# s16_panel_2.net
KiCad netlist of a schematic drawn in EAGLE
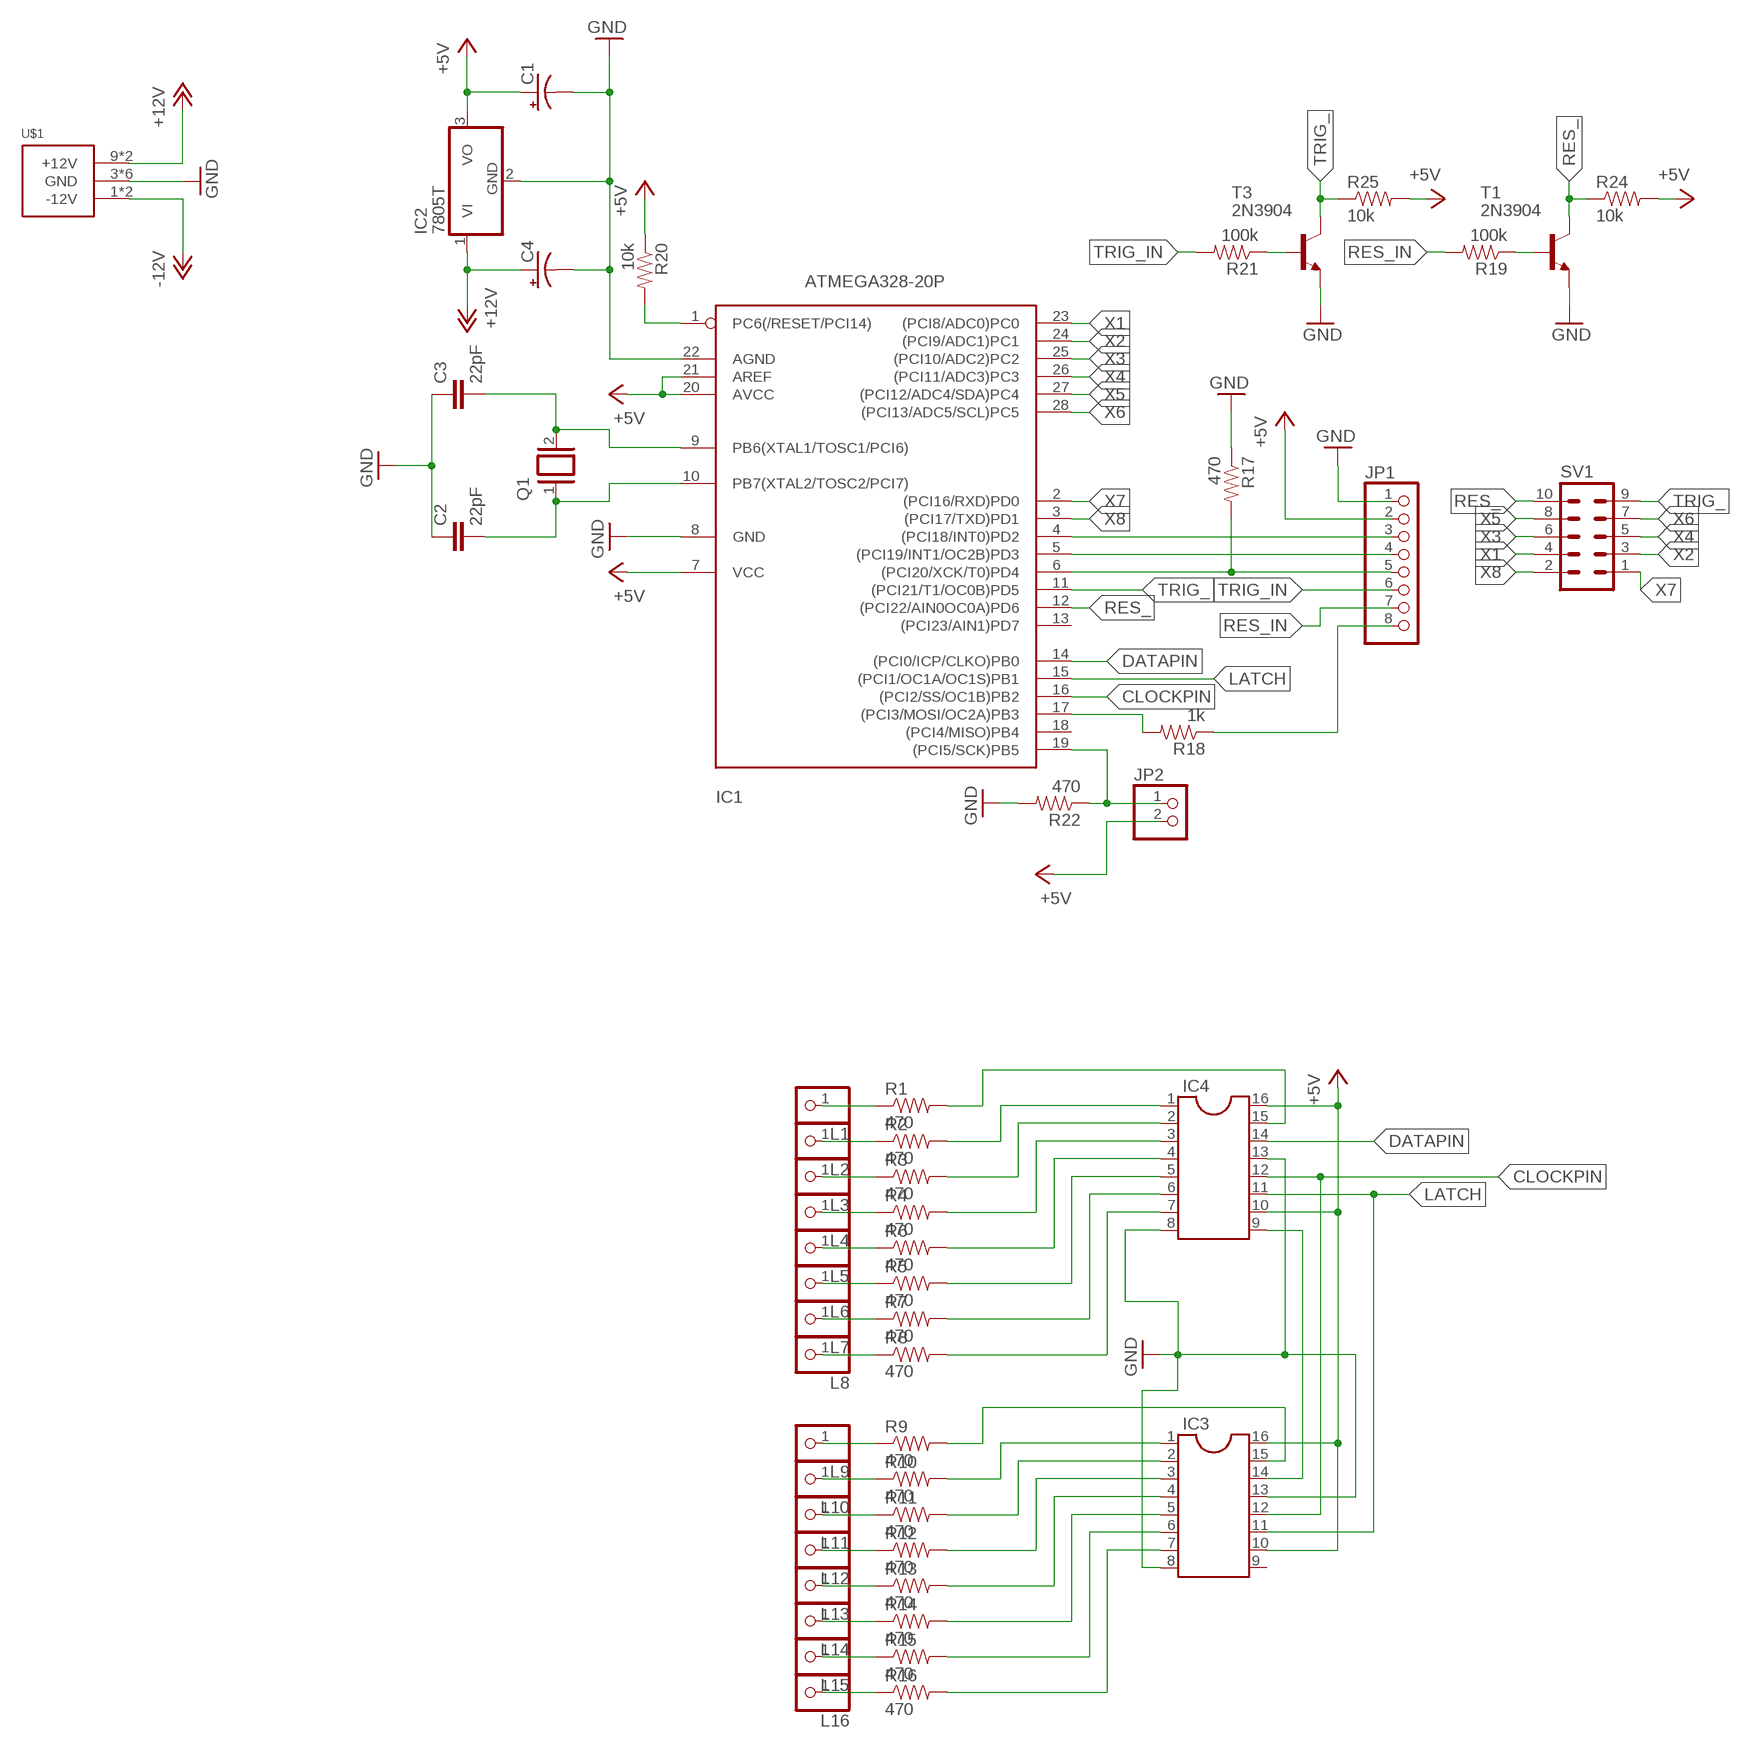
[diagram p0: schematic, sheet 1]

(export (version "E")
  (design (tool "Eeschema 10.0.6"))
  (components
    (comp (ref "C1")
      (value "CAP_POLPTH2")
      (footprint "eagle-import:CPOL-RADIAL-10UF-25V")
      (libsource (lib "eagle-import") (part "CAP_POLPTH2"))
    )
    (comp (ref "C2")
      (value "22pF")
      (footprint "eagle-import:CAP-PTH-SMALLEZ")
      (libsource (lib "eagle-import") (part "CAPEZ"))
    )
    (comp (ref "C3")
      (value "22pF")
      (footprint "eagle-import:CAP-PTH-SMALLEZ")
      (libsource (lib "eagle-import") (part "CAPEZ"))
    )
    (comp (ref "C4")
      (value "CAP_POLPTH2")
      (footprint "eagle-import:CPOL-RADIAL-10UF-25V")
      (libsource (lib "eagle-import") (part "CAP_POLPTH2"))
    )
    (comp (ref "IC1")
      (value "ATMEGA328-20P")
      (footprint "eagle-import:DIL28-3")
      (libsource (lib "eagle-import") (part "ATMEGA328P-20"))
    )
    (comp (ref "IC2")
      (value "7805T")
      (footprint "eagle-import:TO220H")
      (libsource (lib "eagle-import") (part "78T05"))
    )
    (comp (ref "IC3")
      (value "DIL16")
      (footprint "eagle-import:DIL16")
      (libsource (lib "eagle-import") (part "DIL16"))
    )
    (comp (ref "IC4")
      (value "DIL16")
      (footprint "eagle-import:DIL16")
      (libsource (lib "eagle-import") (part "DIL16"))
    )
    (comp (ref "JP1")
      (value "PINHD-1X8BIG")
      (footprint "eagle-import:1X08-BIG")
      (libsource (lib "eagle-import") (part "PINHD-1X8BIG"))
    )
    (comp (ref "JP2")
      (value "PINHD-1X2")
      (footprint "eagle-import:1X02")
      (libsource (lib "eagle-import") (part "PINHD-1X2"))
    )
    (comp (ref "L1")
      (value "PINHD-1X1")
      (footprint "eagle-import:1X01")
      (libsource (lib "eagle-import") (part "PINHD-1X1"))
    )
    (comp (ref "L2")
      (value "PINHD-1X1")
      (footprint "eagle-import:1X01")
      (libsource (lib "eagle-import") (part "PINHD-1X1"))
    )
    (comp (ref "L3")
      (value "PINHD-1X1")
      (footprint "eagle-import:1X01")
      (libsource (lib "eagle-import") (part "PINHD-1X1"))
    )
    (comp (ref "L4")
      (value "PINHD-1X1")
      (footprint "eagle-import:1X01")
      (libsource (lib "eagle-import") (part "PINHD-1X1"))
    )
    (comp (ref "L5")
      (value "PINHD-1X1")
      (footprint "eagle-import:1X01")
      (libsource (lib "eagle-import") (part "PINHD-1X1"))
    )
    (comp (ref "L6")
      (value "PINHD-1X1")
      (footprint "eagle-import:1X01")
      (libsource (lib "eagle-import") (part "PINHD-1X1"))
    )
    (comp (ref "L7")
      (value "PINHD-1X1")
      (footprint "eagle-import:1X01")
      (libsource (lib "eagle-import") (part "PINHD-1X1"))
    )
    (comp (ref "L8")
      (value "PINHD-1X1")
      (footprint "eagle-import:1X01")
      (libsource (lib "eagle-import") (part "PINHD-1X1"))
    )
    (comp (ref "L9")
      (value "PINHD-1X1")
      (footprint "eagle-import:1X01")
      (libsource (lib "eagle-import") (part "PINHD-1X1"))
    )
    (comp (ref "L10")
      (value "PINHD-1X1")
      (footprint "eagle-import:1X01")
      (libsource (lib "eagle-import") (part "PINHD-1X1"))
    )
    (comp (ref "L11")
      (value "PINHD-1X1")
      (footprint "eagle-import:1X01")
      (libsource (lib "eagle-import") (part "PINHD-1X1"))
    )
    (comp (ref "L12")
      (value "PINHD-1X1")
      (footprint "eagle-import:1X01")
      (libsource (lib "eagle-import") (part "PINHD-1X1"))
    )
    (comp (ref "L13")
      (value "PINHD-1X1")
      (footprint "eagle-import:1X01")
      (libsource (lib "eagle-import") (part "PINHD-1X1"))
    )
    (comp (ref "L14")
      (value "PINHD-1X1")
      (footprint "eagle-import:1X01")
      (libsource (lib "eagle-import") (part "PINHD-1X1"))
    )
    (comp (ref "L15")
      (value "PINHD-1X1")
      (footprint "eagle-import:1X01")
      (libsource (lib "eagle-import") (part "PINHD-1X1"))
    )
    (comp (ref "L16")
      (value "PINHD-1X1")
      (footprint "eagle-import:1X01")
      (libsource (lib "eagle-import") (part "PINHD-1X1"))
    )
    (comp (ref "Q1")
      (value "XTAL/S")
      (footprint "eagle-import:QS")
      (libsource (lib "eagle-import") (part "XTAL/S"))
    )
    (comp (ref "R1")
      (value "470")
      (footprint "eagle-import:AXIAL-0.3")
      (libsource (lib "eagle-import") (part "RESISTOR"))
    )
    (comp (ref "R2")
      (value "470")
      (footprint "eagle-import:AXIAL-0.3")
      (libsource (lib "eagle-import") (part "RESISTORAXIAL-0.3"))
    )
    (comp (ref "R3")
      (value "470")
      (footprint "eagle-import:AXIAL-0.3")
      (libsource (lib "eagle-import") (part "RESISTORAXIAL-0.3"))
    )
    (comp (ref "R4")
      (value "470")
      (footprint "eagle-import:AXIAL-0.3")
      (libsource (lib "eagle-import") (part "RESISTORAXIAL-0.3"))
    )
    (comp (ref "R5")
      (value "470")
      (footprint "eagle-import:AXIAL-0.3")
      (libsource (lib "eagle-import") (part "RESISTORAXIAL-0.3"))
    )
    (comp (ref "R6")
      (value "470")
      (footprint "eagle-import:AXIAL-0.3")
      (libsource (lib "eagle-import") (part "RESISTORAXIAL-0.3"))
    )
    (comp (ref "R7")
      (value "470")
      (footprint "eagle-import:AXIAL-0.3")
      (libsource (lib "eagle-import") (part "RESISTORAXIAL-0.3"))
    )
    (comp (ref "R8")
      (value "470")
      (footprint "eagle-import:AXIAL-0.3")
      (libsource (lib "eagle-import") (part "RESISTORAXIAL-0.3"))
    )
    (comp (ref "R9")
      (value "470")
      (footprint "eagle-import:AXIAL-0.3")
      (libsource (lib "eagle-import") (part "RESISTORAXIAL-0.3"))
    )
    (comp (ref "R10")
      (value "470")
      (footprint "eagle-import:AXIAL-0.3")
      (libsource (lib "eagle-import") (part "RESISTORAXIAL-0.3"))
    )
    (comp (ref "R11")
      (value "470")
      (footprint "eagle-import:AXIAL-0.3")
      (libsource (lib "eagle-import") (part "RESISTORAXIAL-0.3"))
    )
    (comp (ref "R12")
      (value "470")
      (footprint "eagle-import:AXIAL-0.3")
      (libsource (lib "eagle-import") (part "RESISTORAXIAL-0.3"))
    )
    (comp (ref "R13")
      (value "470")
      (footprint "eagle-import:AXIAL-0.3")
      (libsource (lib "eagle-import") (part "RESISTORAXIAL-0.3"))
    )
    (comp (ref "R14")
      (value "470")
      (footprint "eagle-import:AXIAL-0.3")
      (libsource (lib "eagle-import") (part "RESISTORAXIAL-0.3"))
    )
    (comp (ref "R15")
      (value "470")
      (footprint "eagle-import:AXIAL-0.3")
      (libsource (lib "eagle-import") (part "RESISTORAXIAL-0.3"))
    )
    (comp (ref "R16")
      (value "470")
      (footprint "eagle-import:AXIAL-0.3")
      (libsource (lib "eagle-import") (part "RESISTORAXIAL-0.3"))
    )
    (comp (ref "R17")
      (value "470")
      (footprint "eagle-import:AXIAL-0.3")
      (libsource (lib "eagle-import") (part "RESISTORAXIAL-0.3"))
    )
    (comp (ref "R18")
      (value "1k")
      (footprint "eagle-import:AXIAL-0.3")
      (libsource (lib "eagle-import") (part "RESISTORAXIAL-0.3"))
    )
    (comp (ref "R19")
      (value "100k")
      (footprint "eagle-import:AXIAL-0.3")
      (libsource (lib "eagle-import") (part "RESISTORAXIAL-0.3"))
    )
    (comp (ref "R20")
      (value "10k")
      (footprint "eagle-import:AXIAL-0.3")
      (libsource (lib "eagle-import") (part "RESISTORAXIAL-0.3"))
    )
    (comp (ref "R21")
      (value "100k")
      (footprint "eagle-import:AXIAL-0.3")
      (libsource (lib "eagle-import") (part "RESISTORAXIAL-0.3"))
    )
    (comp (ref "R22")
      (value "470")
      (footprint "eagle-import:AXIAL-0.3")
      (libsource (lib "eagle-import") (part "RESISTOR"))
    )
    (comp (ref "R24")
      (value "10k")
      (footprint "eagle-import:AXIAL-0.3")
      (libsource (lib "eagle-import") (part "RESISTORAXIAL-0.3"))
    )
    (comp (ref "R25")
      (value "10k")
      (footprint "eagle-import:AXIAL-0.3")
      (libsource (lib "eagle-import") (part "RESISTORAXIAL-0.3"))
    )
    (comp (ref "SV1")
      (value "MA05-2")
      (footprint "eagle-import:MA05-2")
      (libsource (lib "eagle-import") (part "MA05-2"))
    )
    (comp (ref "T1")
      (value "2N3904")
      (footprint "eagle-import:TO92")
      (libsource (lib "eagle-import") (part "2N3904"))
    )
    (comp (ref "T3")
      (value "2N3904")
      (footprint "eagle-import:TO92")
      (libsource (lib "eagle-import") (part "2N3904"))
    )
    (comp (ref "U$1")
      (value "POWER_SIMPLE10")
      (footprint "eagle-import:POWER_10")
      (libsource (lib "eagle-import") (part "POWER_SIMPLE10"))
    )
  )
  (nets
    (net (code "1") (name "+5V") (class "Default")
      (node (ref "C1") (pin "1") (pinfunction "+_1") (pintype "passive"))
      (node (ref "IC1") (pin "20") (pinfunction "AVCC_20") (pintype "bidirectional"))
      (node (ref "IC1") (pin "21") (pinfunction "AREF_21") (pintype "bidirectional"))
      (node (ref "IC1") (pin "7") (pinfunction "VCC_7") (pintype "bidirectional"))
      (node (ref "IC2") (pin "3") (pinfunction "VO_3") (pintype "passive"))
      (node (ref "IC3") (pin "10") (pinfunction "10_10") (pintype "passive"))
      (node (ref "IC3") (pin "16") (pinfunction "16_16") (pintype "passive"))
      (node (ref "IC4") (pin "10") (pinfunction "10_10") (pintype "passive"))
      (node (ref "IC4") (pin "16") (pinfunction "16_16") (pintype "passive"))
      (node (ref "JP1") (pin "2") (pinfunction "2_2") (pintype "passive"))
      (node (ref "JP2") (pin "2") (pinfunction "2_2") (pintype "passive"))
      (node (ref "R20") (pin "P$1") (pinfunction "1_P$1") (pintype "passive"))
      (node (ref "R24") (pin "P$2") (pinfunction "2_P$2") (pintype "passive"))
      (node (ref "R25") (pin "P$2") (pinfunction "2_P$2") (pintype "passive"))
    )
    (net (code "2") (name "+12V") (class "Default")
      (node (ref "C4") (pin "1") (pinfunction "+_1") (pintype "passive"))
      (node (ref "IC2") (pin "1") (pinfunction "VI_1") (pintype "input"))
      (node (ref "U$1") (pin "10") (pinfunction "+12V_10") (pintype "bidirectional"))
      (node (ref "U$1") (pin "9") (pinfunction "+12V_9") (pintype "bidirectional"))
    )
    (net (code "3") (name "-12V") (class "Default")
      (node (ref "U$1") (pin "1") (pinfunction "-12V_1") (pintype "bidirectional"))
      (node (ref "U$1") (pin "2") (pinfunction "-12V_2") (pintype "bidirectional"))
    )
    (net (code "4") (name "CLOCKPIN") (class "Default")
      (node (ref "IC1") (pin "16") (pinfunction "(PCI2/SS/OC1B)PB2_16") (pintype "bidirectional"))
      (node (ref "IC3") (pin "12") (pinfunction "12_12") (pintype "passive"))
      (node (ref "IC4") (pin "12") (pinfunction "12_12") (pintype "passive"))
    )
    (net (code "5") (name "DATAPIN") (class "Default")
      (node (ref "IC1") (pin "14") (pinfunction "(PCI0/ICP/CLKO)PB0_14") (pintype "bidirectional"))
      (node (ref "IC4") (pin "14") (pinfunction "14_14") (pintype "passive"))
    )
    (net (code "6") (name "GND") (class "Default")
      (node (ref "C1") (pin "2") (pinfunction "-_2") (pintype "passive"))
      (node (ref "C2") (pin "1") (pinfunction "1_1") (pintype "passive"))
      (node (ref "C3") (pin "1") (pinfunction "1_1") (pintype "passive"))
      (node (ref "C4") (pin "2") (pinfunction "-_2") (pintype "passive"))
      (node (ref "IC1") (pin "22") (pinfunction "AGND_22") (pintype "bidirectional"))
      (node (ref "IC1") (pin "8") (pinfunction "GND_8") (pintype "bidirectional"))
      (node (ref "IC2") (pin "2") (pinfunction "GND_2") (pintype "passive"))
      (node (ref "IC3") (pin "13") (pinfunction "13_13") (pintype "passive"))
      (node (ref "IC3") (pin "8") (pinfunction "8_8") (pintype "passive"))
      (node (ref "IC4") (pin "13") (pinfunction "13_13") (pintype "passive"))
      (node (ref "IC4") (pin "8") (pinfunction "8_8") (pintype "passive"))
      (node (ref "JP1") (pin "1") (pinfunction "1_1") (pintype "passive"))
      (node (ref "R17") (pin "P$1") (pinfunction "1_P$1") (pintype "passive"))
      (node (ref "R22") (pin "P$2") (pinfunction "2_P$2") (pintype "passive"))
      (node (ref "T1") (pin "3") (pinfunction "E_3") (pintype "passive"))
      (node (ref "T3") (pin "3") (pinfunction "E_3") (pintype "passive"))
      (node (ref "U$1") (pin "3") (pinfunction "GND_3") (pintype "bidirectional"))
      (node (ref "U$1") (pin "4") (pinfunction "GND_4") (pintype "bidirectional"))
      (node (ref "U$1") (pin "5") (pinfunction "GND_5") (pintype "bidirectional"))
      (node (ref "U$1") (pin "6") (pinfunction "GND_6") (pintype "bidirectional"))
      (node (ref "U$1") (pin "7") (pinfunction "GND_7") (pintype "bidirectional"))
      (node (ref "U$1") (pin "8") (pinfunction "GND_8") (pintype "bidirectional"))
    )
    (net (code "7") (name "LATCH") (class "Default")
      (node (ref "IC1") (pin "15") (pinfunction "(PCI1/OC1A/OC1S)PB1_15") (pintype "bidirectional"))
      (node (ref "IC3") (pin "11") (pinfunction "11_11") (pintype "passive"))
      (node (ref "IC4") (pin "11") (pinfunction "11_11") (pintype "passive"))
    )
    (net (code "8") (name "Net-(IC1-(PCI3{slash}MOSI{slash}OC2A)PB3)") (class "Default")
      (node (ref "IC1") (pin "17") (pinfunction "(PCI3/MOSI/OC2A)PB3_17") (pintype "bidirectional"))
      (node (ref "R18") (pin "P$2") (pinfunction "2_P$2") (pintype "passive"))
    )
    (net (code "9") (name "Net-(IC1-(PCI5{slash}SCK)PB5)") (class "Default")
      (node (ref "IC1") (pin "19") (pinfunction "(PCI5/SCK)PB5_19") (pintype "bidirectional"))
      (node (ref "JP2") (pin "1") (pinfunction "1_1") (pintype "passive"))
      (node (ref "R22") (pin "P$1") (pinfunction "1_P$1") (pintype "passive"))
    )
    (net (code "10") (name "Net-(IC1-(PCI18{slash}INT0)PD2)") (class "Default")
      (node (ref "IC1") (pin "4") (pinfunction "(PCI18/INT0)PD2_4") (pintype "bidirectional"))
      (node (ref "JP1") (pin "3") (pinfunction "3_3") (pintype "passive"))
    )
    (net (code "11") (name "Net-(IC1-(PCI19{slash}INT1{slash}OC2B)PD3)") (class "Default")
      (node (ref "IC1") (pin "5") (pinfunction "(PCI19/INT1/OC2B)PD3_5") (pintype "bidirectional"))
      (node (ref "JP1") (pin "4") (pinfunction "4_4") (pintype "passive"))
    )
    (net (code "12") (name "Net-(IC1-(PCI20{slash}XCK{slash}T0)PD4)") (class "Default")
      (node (ref "IC1") (pin "6") (pinfunction "(PCI20/XCK/T0)PD4_6") (pintype "bidirectional"))
      (node (ref "JP1") (pin "5") (pinfunction "5_5") (pintype "passive"))
      (node (ref "R17") (pin "P$2") (pinfunction "2_P$2") (pintype "passive"))
    )
    (net (code "13") (name "Net-(IC1-PB6(XTAL1{slash}TOSC1{slash}PCI6))") (class "Default")
      (node (ref "C3") (pin "2") (pinfunction "2_2") (pintype "passive"))
      (node (ref "IC1") (pin "9") (pinfunction "PB6(XTAL1/TOSC1/PCI6)_9") (pintype "bidirectional"))
      (node (ref "Q1") (pin "2") (pinfunction "2_2") (pintype "passive"))
    )
    (net (code "14") (name "Net-(IC1-PB7(XTAL2{slash}TOSC2{slash}PCI7))") (class "Default")
      (node (ref "C2") (pin "2") (pinfunction "2_2") (pintype "passive"))
      (node (ref "IC1") (pin "10") (pinfunction "PB7(XTAL2/TOSC2/PCI7)_10") (pintype "bidirectional"))
      (node (ref "Q1") (pin "1") (pinfunction "1_1") (pintype "passive"))
    )
    (net (code "15") (name "Net-(IC1-PC6({slash}RESET{slash}PCI14))") (class "Default")
      (node (ref "IC1") (pin "1") (pinfunction "PC6(/RESET/PCI14)_1") (pintype "bidirectional"))
      (node (ref "R20") (pin "P$2") (pinfunction "2_P$2") (pintype "passive"))
    )
    (net (code "16") (name "Net-(IC3-Pad14)") (class "Default")
      (node (ref "IC3") (pin "14") (pinfunction "14_14") (pintype "passive"))
      (node (ref "IC4") (pin "9") (pinfunction "9_9") (pintype "passive"))
    )
    (net (code "17") (name "Net-(R1-1)") (class "Default")
      (node (ref "L1") (pin "1") (pinfunction "1_1") (pintype "passive"))
      (node (ref "R1") (pin "P$1") (pinfunction "1_P$1") (pintype "passive"))
    )
    (net (code "18") (name "Net-(R1-2)") (class "Default")
      (node (ref "IC4") (pin "15") (pinfunction "15_15") (pintype "passive"))
      (node (ref "R1") (pin "P$2") (pinfunction "2_P$2") (pintype "passive"))
    )
    (net (code "19") (name "Net-(R2-1)") (class "Default")
      (node (ref "L2") (pin "1") (pinfunction "1_1") (pintype "passive"))
      (node (ref "R2") (pin "P$1") (pinfunction "1_P$1") (pintype "passive"))
    )
    (net (code "20") (name "Net-(R2-2)") (class "Default")
      (node (ref "IC4") (pin "1") (pinfunction "1_1") (pintype "passive"))
      (node (ref "R2") (pin "P$2") (pinfunction "2_P$2") (pintype "passive"))
    )
    (net (code "21") (name "Net-(R3-1)") (class "Default")
      (node (ref "L3") (pin "1") (pinfunction "1_1") (pintype "passive"))
      (node (ref "R3") (pin "P$1") (pinfunction "1_P$1") (pintype "passive"))
    )
    (net (code "22") (name "Net-(R3-2)") (class "Default")
      (node (ref "IC4") (pin "2") (pinfunction "2_2") (pintype "passive"))
      (node (ref "R3") (pin "P$2") (pinfunction "2_P$2") (pintype "passive"))
    )
    (net (code "23") (name "Net-(R4-1)") (class "Default")
      (node (ref "L4") (pin "1") (pinfunction "1_1") (pintype "passive"))
      (node (ref "R4") (pin "P$1") (pinfunction "1_P$1") (pintype "passive"))
    )
    (net (code "24") (name "Net-(R4-2)") (class "Default")
      (node (ref "IC4") (pin "3") (pinfunction "3_3") (pintype "passive"))
      (node (ref "R4") (pin "P$2") (pinfunction "2_P$2") (pintype "passive"))
    )
    (net (code "25") (name "Net-(R5-1)") (class "Default")
      (node (ref "L6") (pin "1") (pinfunction "1_1") (pintype "passive"))
      (node (ref "R5") (pin "P$1") (pinfunction "1_P$1") (pintype "passive"))
    )
    (net (code "26") (name "Net-(R5-2)") (class "Default")
      (node (ref "IC4") (pin "5") (pinfunction "5_5") (pintype "passive"))
      (node (ref "R5") (pin "P$2") (pinfunction "2_P$2") (pintype "passive"))
    )
    (net (code "27") (name "Net-(R6-1)") (class "Default")
      (node (ref "L5") (pin "1") (pinfunction "1_1") (pintype "passive"))
      (node (ref "R6") (pin "P$1") (pinfunction "1_P$1") (pintype "passive"))
    )
    (net (code "28") (name "Net-(R6-2)") (class "Default")
      (node (ref "IC4") (pin "4") (pinfunction "4_4") (pintype "passive"))
      (node (ref "R6") (pin "P$2") (pinfunction "2_P$2") (pintype "passive"))
    )
    (net (code "29") (name "Net-(R7-1)") (class "Default")
      (node (ref "L7") (pin "1") (pinfunction "1_1") (pintype "passive"))
      (node (ref "R7") (pin "P$1") (pinfunction "1_P$1") (pintype "passive"))
    )
    (net (code "30") (name "Net-(R7-2)") (class "Default")
      (node (ref "IC4") (pin "6") (pinfunction "6_6") (pintype "passive"))
      (node (ref "R7") (pin "P$2") (pinfunction "2_P$2") (pintype "passive"))
    )
    (net (code "31") (name "Net-(R8-1)") (class "Default")
      (node (ref "L8") (pin "1") (pinfunction "1_1") (pintype "passive"))
      (node (ref "R8") (pin "P$1") (pinfunction "1_P$1") (pintype "passive"))
    )
    (net (code "32") (name "Net-(R8-2)") (class "Default")
      (node (ref "IC4") (pin "7") (pinfunction "7_7") (pintype "passive"))
      (node (ref "R8") (pin "P$2") (pinfunction "2_P$2") (pintype "passive"))
    )
    (net (code "33") (name "Net-(R9-1)") (class "Default")
      (node (ref "L9") (pin "1") (pinfunction "1_1") (pintype "passive"))
      (node (ref "R9") (pin "P$1") (pinfunction "1_P$1") (pintype "passive"))
    )
    (net (code "34") (name "Net-(R9-2)") (class "Default")
      (node (ref "IC3") (pin "15") (pinfunction "15_15") (pintype "passive"))
      (node (ref "R9") (pin "P$2") (pinfunction "2_P$2") (pintype "passive"))
    )
    (net (code "35") (name "Net-(R10-1)") (class "Default")
      (node (ref "L10") (pin "1") (pinfunction "1_1") (pintype "passive"))
      (node (ref "R10") (pin "P$1") (pinfunction "1_P$1") (pintype "passive"))
    )
    (net (code "36") (name "Net-(R10-2)") (class "Default")
      (node (ref "IC3") (pin "1") (pinfunction "1_1") (pintype "passive"))
      (node (ref "R10") (pin "P$2") (pinfunction "2_P$2") (pintype "passive"))
    )
    (net (code "37") (name "Net-(R11-1)") (class "Default")
      (node (ref "L11") (pin "1") (pinfunction "1_1") (pintype "passive"))
      (node (ref "R11") (pin "P$1") (pinfunction "1_P$1") (pintype "passive"))
    )
    (net (code "38") (name "Net-(R11-2)") (class "Default")
      (node (ref "IC3") (pin "2") (pinfunction "2_2") (pintype "passive"))
      (node (ref "R11") (pin "P$2") (pinfunction "2_P$2") (pintype "passive"))
    )
    (net (code "39") (name "Net-(R12-1)") (class "Default")
      (node (ref "L12") (pin "1") (pinfunction "1_1") (pintype "passive"))
      (node (ref "R12") (pin "P$1") (pinfunction "1_P$1") (pintype "passive"))
    )
    (net (code "40") (name "Net-(R12-2)") (class "Default")
      (node (ref "IC3") (pin "3") (pinfunction "3_3") (pintype "passive"))
      (node (ref "R12") (pin "P$2") (pinfunction "2_P$2") (pintype "passive"))
    )
    (net (code "41") (name "Net-(R13-1)") (class "Default")
      (node (ref "L13") (pin "1") (pinfunction "1_1") (pintype "passive"))
      (node (ref "R13") (pin "P$1") (pinfunction "1_P$1") (pintype "passive"))
    )
    (net (code "42") (name "Net-(R13-2)") (class "Default")
      (node (ref "IC3") (pin "4") (pinfunction "4_4") (pintype "passive"))
      (node (ref "R13") (pin "P$2") (pinfunction "2_P$2") (pintype "passive"))
    )
    (net (code "43") (name "Net-(R14-1)") (class "Default")
      (node (ref "L14") (pin "1") (pinfunction "1_1") (pintype "passive"))
      (node (ref "R14") (pin "P$1") (pinfunction "1_P$1") (pintype "passive"))
    )
    (net (code "44") (name "Net-(R14-2)") (class "Default")
      (node (ref "IC3") (pin "5") (pinfunction "5_5") (pintype "passive"))
      (node (ref "R14") (pin "P$2") (pinfunction "2_P$2") (pintype "passive"))
    )
    (net (code "45") (name "Net-(R15-1)") (class "Default")
      (node (ref "L15") (pin "1") (pinfunction "1_1") (pintype "passive"))
      (node (ref "R15") (pin "P$1") (pinfunction "1_P$1") (pintype "passive"))
    )
    (net (code "46") (name "Net-(R15-2)") (class "Default")
      (node (ref "IC3") (pin "6") (pinfunction "6_6") (pintype "passive"))
      (node (ref "R15") (pin "P$2") (pinfunction "2_P$2") (pintype "passive"))
    )
    (net (code "47") (name "Net-(R16-1)") (class "Default")
      (node (ref "L16") (pin "1") (pinfunction "1_1") (pintype "passive"))
      (node (ref "R16") (pin "P$1") (pinfunction "1_P$1") (pintype "passive"))
    )
    (net (code "48") (name "Net-(R16-2)") (class "Default")
      (node (ref "IC3") (pin "7") (pinfunction "7_7") (pintype "passive"))
      (node (ref "R16") (pin "P$2") (pinfunction "2_P$2") (pintype "passive"))
    )
    (net (code "49") (name "Net-(R18-1)") (class "Default")
      (node (ref "JP1") (pin "8") (pinfunction "8_8") (pintype "passive"))
      (node (ref "R18") (pin "P$1") (pinfunction "1_P$1") (pintype "passive"))
    )
    (net (code "50") (name "Net-(R19-1)") (class "Default")
      (node (ref "R19") (pin "P$1") (pinfunction "1_P$1") (pintype "passive"))
      (node (ref "T1") (pin "2") (pinfunction "B_2") (pintype "passive"))
    )
    (net (code "51") (name "Net-(R21-1)") (class "Default")
      (node (ref "R21") (pin "P$1") (pinfunction "1_P$1") (pintype "passive"))
      (node (ref "T3") (pin "2") (pinfunction "B_2") (pintype "passive"))
    )
    (net (code "52") (name "RES_") (class "Default")
      (node (ref "IC1") (pin "12") (pinfunction "(PCI22/AIN0OC0A)PD6_12") (pintype "bidirectional"))
      (node (ref "R24") (pin "P$1") (pinfunction "1_P$1") (pintype "passive"))
      (node (ref "SV1") (pin "10") (pinfunction "10_10") (pintype "passive"))
      (node (ref "T1") (pin "1") (pinfunction "C_1") (pintype "passive"))
    )
    (net (code "53") (name "RES_IN") (class "Default")
      (node (ref "JP1") (pin "7") (pinfunction "7_7") (pintype "passive"))
      (node (ref "R19") (pin "P$2") (pinfunction "2_P$2") (pintype "passive"))
    )
    (net (code "54") (name "TRIG_") (class "Default")
      (node (ref "IC1") (pin "11") (pinfunction "(PCI21/T1/OC0B)PD5_11") (pintype "bidirectional"))
      (node (ref "R25") (pin "P$1") (pinfunction "1_P$1") (pintype "passive"))
      (node (ref "SV1") (pin "9") (pinfunction "9_9") (pintype "passive"))
      (node (ref "T3") (pin "1") (pinfunction "C_1") (pintype "passive"))
    )
    (net (code "55") (name "TRIG_IN") (class "Default")
      (node (ref "JP1") (pin "6") (pinfunction "6_6") (pintype "passive"))
      (node (ref "R21") (pin "P$2") (pinfunction "2_P$2") (pintype "passive"))
    )
    (net (code "56") (name "X1") (class "Default")
      (node (ref "IC1") (pin "23") (pinfunction "(PCI8/ADC0)PC0_23") (pintype "bidirectional"))
      (node (ref "SV1") (pin "4") (pinfunction "4_4") (pintype "passive"))
    )
    (net (code "57") (name "X2") (class "Default")
      (node (ref "IC1") (pin "24") (pinfunction "(PCI9/ADC1)PC1_24") (pintype "bidirectional"))
      (node (ref "SV1") (pin "3") (pinfunction "3_3") (pintype "passive"))
    )
    (net (code "58") (name "X3") (class "Default")
      (node (ref "IC1") (pin "25") (pinfunction "(PCI10/ADC2)PC2_25") (pintype "bidirectional"))
      (node (ref "SV1") (pin "6") (pinfunction "6_6") (pintype "passive"))
    )
    (net (code "59") (name "X4") (class "Default")
      (node (ref "IC1") (pin "26") (pinfunction "(PCI11/ADC3)PC3_26") (pintype "bidirectional"))
      (node (ref "SV1") (pin "5") (pinfunction "5_5") (pintype "passive"))
    )
    (net (code "60") (name "X5") (class "Default")
      (node (ref "IC1") (pin "27") (pinfunction "(PCI12/ADC4/SDA)PC4_27") (pintype "bidirectional"))
      (node (ref "SV1") (pin "8") (pinfunction "8_8") (pintype "passive"))
    )
    (net (code "61") (name "X6") (class "Default")
      (node (ref "IC1") (pin "28") (pinfunction "(PCI13/ADC5/SCL)PC5_28") (pintype "bidirectional"))
      (node (ref "SV1") (pin "7") (pinfunction "7_7") (pintype "passive"))
    )
    (net (code "62") (name "X7") (class "Default")
      (node (ref "IC1") (pin "2") (pinfunction "(PCI16/RXD)PD0_2") (pintype "bidirectional"))
      (node (ref "SV1") (pin "1") (pinfunction "1_1") (pintype "passive"))
    )
    (net (code "63") (name "X8") (class "Default")
      (node (ref "IC1") (pin "3") (pinfunction "(PCI17/TXD)PD1_3") (pintype "bidirectional"))
      (node (ref "SV1") (pin "2") (pinfunction "2_2") (pintype "passive"))
    )
    (net (code "64") (name "unconnected-(IC1-(PCI4{slash}MISO)PB4-Pad18)") (class "Default")
      (node (ref "IC1") (pin "18") (pinfunction "(PCI4/MISO)PB4_18") (pintype "bidirectional"))
    )
    (net (code "65") (name "unconnected-(IC1-(PCI23{slash}AIN1)PD7-Pad13)") (class "Default")
      (node (ref "IC1") (pin "13") (pinfunction "(PCI23/AIN1)PD7_13") (pintype "bidirectional"))
    )
    (net (code "66") (name "unconnected-(IC3-Pad9)") (class "Default")
      (node (ref "IC3") (pin "9") (pinfunction "9_9") (pintype "passive"))
    )
  )
)
